# Peripherals.net
KiCad netlist of a schematic drawn in Altium Designer
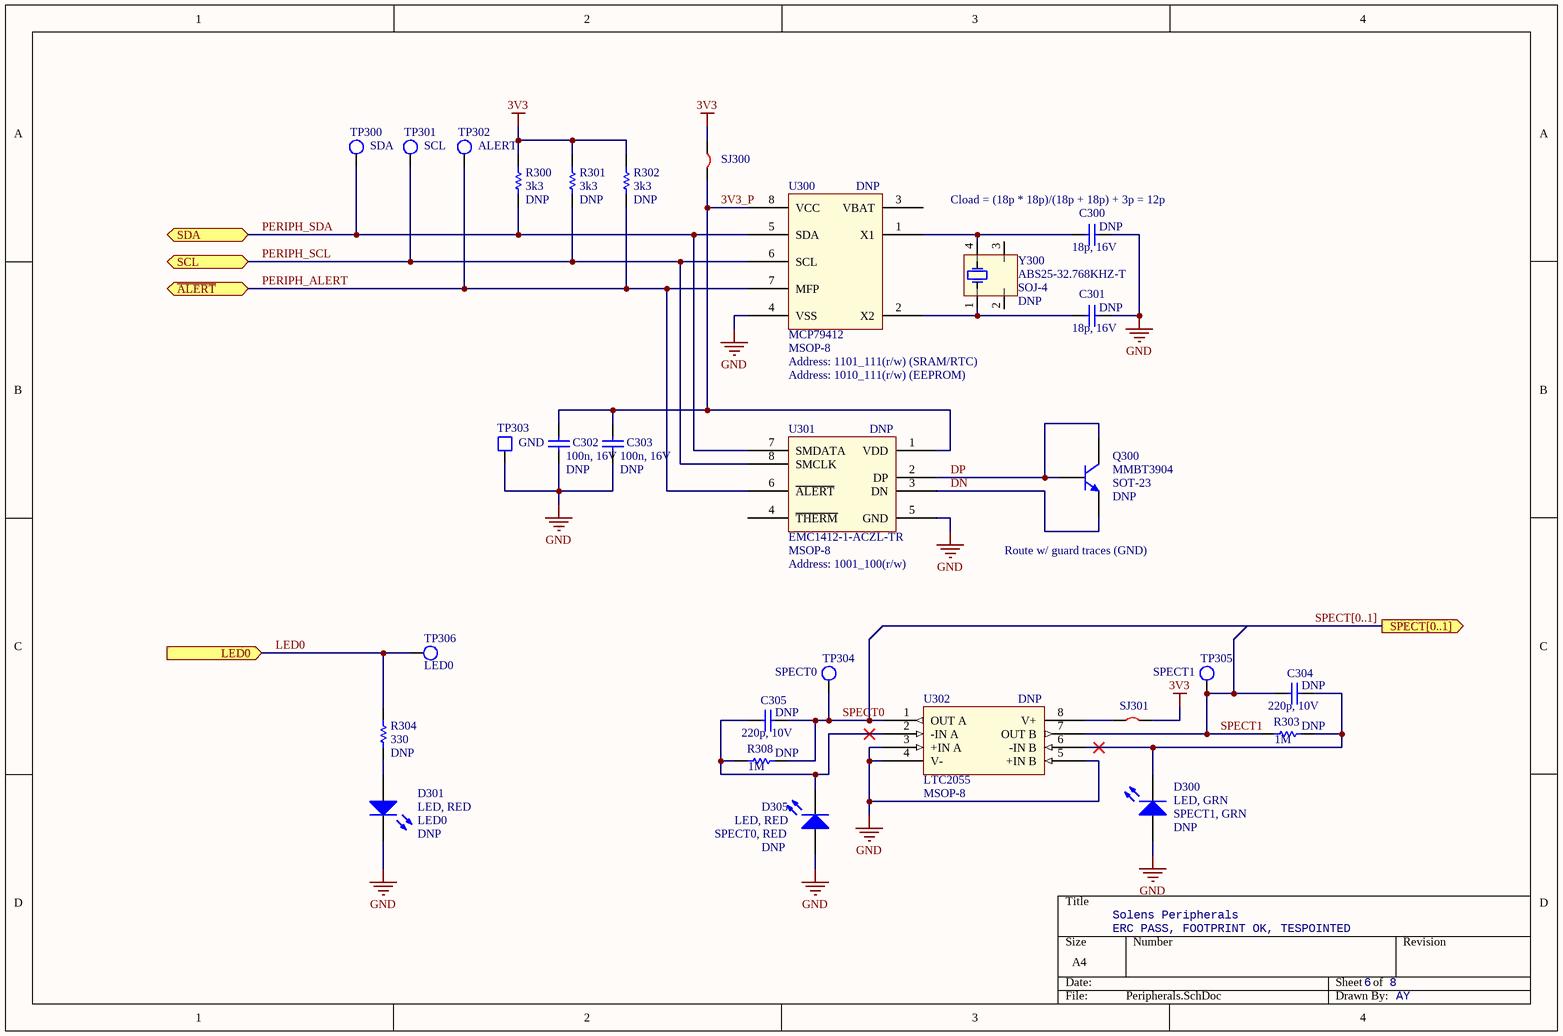
[diagram p0: Peripherals.SchDoc]

(export (version "E")
  (design (tool "Eeschema 10.0.6"))
  (components
    (comp (ref "C300")
      (value "18p, 16V")
      (footprint "CAP_0402")
      (description "Capacitor")
      (fields (field (name "DNP") "DNP") (field (name "Comment") "18p, 16V, 0402 (DNP)"))
      (libsource (lib "Miscellaneous Devices") (part "Cap"))
    )
    (comp (ref "C301")
      (value "18p, 16V")
      (footprint "CAP_0402")
      (description "Capacitor")
      (fields (field (name "DNP") "DNP") (field (name "Comment") "18p, 16V, 0402 (DNP)"))
      (libsource (lib "Miscellaneous Devices") (part "Cap"))
    )
    (comp (ref "C302")
      (value "100n, 16V")
      (footprint "CAP_0402")
      (description "Capacitor")
      (fields (field (name "DNP") "DNP") (field (name "Comment") "100n, 16V, 0402 (DNP)"))
      (libsource (lib "Miscellaneous Devices") (part "Cap"))
    )
    (comp (ref "C303")
      (value "100n, 16V")
      (footprint "CAP_0402")
      (description "Capacitor")
      (fields (field (name "DNP") "DNP") (field (name "Comment") "100n, 16V, 0402 (DNP)"))
      (libsource (lib "Miscellaneous Devices") (part "Cap"))
    )
    (comp (ref "C304")
      (value "220p, 10V")
      (footprint "CAP_0402")
      (description "Capacitor")
      (fields (field (name "DNP") "DNP") (field (name "Comment") "220p, 16V, 0402 (DNP)"))
      (libsource (lib "Miscellaneous Devices") (part "Cap"))
    )
    (comp (ref "C305")
      (value "220p, 10V")
      (footprint "CAP_0402")
      (description "Capacitor")
      (fields (field (name "DNP") "DNP") (field (name "Comment") "220p, 16V, 0402 (DNP)"))
      (libsource (lib "Miscellaneous Devices") (part "Cap"))
    )
    (comp (ref "D300")
      (value "LED, GRN")
      (footprint "LED_0603")
      (description "Typical INFRARED GaAs LED")
      (fields
        (field (name "DNP") "DNP")
        (field (name "FUNCTION") "SPECT1, GRN")
        (field (name "Comment") "LED, GRN, 0603 (DNP)")
      )
      (libsource (lib "Miscellaneous Devices") (part "LED0"))
    )
    (comp (ref "D301")
      (value "LED, RED")
      (footprint "LED_0603")
      (description "Typical INFRARED GaAs LED")
      (fields
        (field (name "DNP") "DNP")
        (field (name "FUNCTION") "LED0")
        (field (name "Comment") "LED, RED, 0603 (DNP)")
      )
      (libsource (lib "Miscellaneous Devices") (part "LED0"))
    )
    (comp (ref "D305")
      (value "LED, RED")
      (footprint "LED_0603")
      (description "Typical INFRARED GaAs LED")
      (fields
        (field (name "DNP") "DNP")
        (field (name "FUNCTION") "SPECT0, RED")
        (field (name "Comment") "LED, RED, 0603 (DNP)")
      )
      (libsource (lib "Miscellaneous Devices") (part "LED0"))
    )
    (comp (ref "Q300")
      (value "MMBT3904, SOT-23 (DNP)")
      (footprint "SOT90P240X110-3N")
      (description "NPN General Purpose Amplifier")
      (fields
        (field (name "PARTNUMBER") "MMBT3904")
        (field (name "PACKAGENAME") "SOT-23")
        (field (name "DNP") "DNP")
      )
      (libsource (lib "Miscellaneous Devices") (part "2N3904"))
    )
    (comp (ref "R300")
      (value "3k3")
      (footprint "RES_0805")
      (description "Resistor")
      (fields (field (name "DNP") "DNP") (field (name "Comment") "3k3, 1/8W, 0805 (DNP)"))
      (libsource (lib "Miscellaneous Devices") (part "Res1"))
    )
    (comp (ref "R301")
      (value "3k3")
      (footprint "RES_0805")
      (description "Resistor")
      (fields (field (name "DNP") "DNP") (field (name "Comment") "3k3, 1/8W, 0805 (DNP)"))
      (libsource (lib "Miscellaneous Devices") (part "Res1"))
    )
    (comp (ref "R302")
      (value "3k3")
      (footprint "RES_0805")
      (description "Resistor")
      (fields (field (name "DNP") "DNP") (field (name "Comment") "3k3, 1/8W, 0805 (DNP)"))
      (libsource (lib "Miscellaneous Devices") (part "Res1"))
    )
    (comp (ref "R303")
      (value "1M")
      (footprint "RES_0402")
      (description "Resistor")
      (fields (field (name "DNP") "DNP") (field (name "Comment") "1M, 1/16W, 0402 (DNP)"))
      (libsource (lib "Miscellaneous Devices") (part "Res1"))
    )
    (comp (ref "R304")
      (value "330")
      (footprint "RES_0805")
      (description "Resistor")
      (fields (field (name "DNP") "DNP") (field (name "Comment") "330, 1/8W, 0805 (DNP)"))
      (libsource (lib "Miscellaneous Devices") (part "Res1"))
    )
    (comp (ref "R308")
      (value "1M")
      (footprint "RES_0402")
      (description "Resistor")
      (fields (field (name "DNP") "DNP") (field (name "Comment") "1M, 1/16W, 0402 (DNP)"))
      (libsource (lib "Miscellaneous Devices") (part "Res1"))
    )
    (comp (ref "SJ300")
      (value "SJ, 0805 (DNP)")
      (footprint "SJ_0805")
      (description "Solder jumper")
      (libsource (lib "Schlib1") (part "SJ"))
    )
    (comp (ref "SJ301")
      (value "SJ, 0805 (DNP)")
      (footprint "SJ_0805")
      (description "Solder jumper")
      (libsource (lib "Schlib1") (part "SJ"))
    )
    (comp (ref "TP300")
      (value "TP (DNP)")
      (footprint "TP_SMALL")
      (fields (field (name "VISIBLENETNAME") "SDA"))
      (libsource (lib "Schlib1") (part "TP_SMALL"))
    )
    (comp (ref "TP301")
      (value "TP (DNP)")
      (footprint "TP_SMALL")
      (fields (field (name "VISIBLENETNAME") "SCL"))
      (libsource (lib "Schlib1") (part "TP_SMALL"))
    )
    (comp (ref "TP302")
      (value "TP (DNP)")
      (footprint "TP_SMALL")
      (fields (field (name "VISIBLENETNAME") "ALERT"))
      (libsource (lib "Schlib1") (part "TP_SMALL"))
    )
    (comp (ref "TP303")
      (value "TP (DNP)")
      (footprint "TP_LARGE")
      (fields (field (name "VISIBLENETNAME") "GND"))
      (libsource (lib "Schlib1") (part "TP_LARGE"))
    )
    (comp (ref "TP304")
      (value "TP (DNP)")
      (footprint "TP_SMALL")
      (fields (field (name "VISIBLENETNAME") "SPECT0"))
      (libsource (lib "Schlib1") (part "TP_SMALL"))
    )
    (comp (ref "TP305")
      (value "TP (DNP)")
      (footprint "TP_SMALL")
      (fields (field (name "VISIBLENETNAME") "SPECT1"))
      (libsource (lib "Schlib1") (part "TP_SMALL"))
    )
    (comp (ref "TP306")
      (value "TP (DNP)")
      (footprint "TP_SMALL")
      (fields (field (name "VISIBLENETNAME") "LED0"))
      (libsource (lib "Schlib1") (part "TP_SMALL"))
    )
    (comp (ref "U300")
      (value "MCP79412, MSOP-8 (DNP)")
      (footprint "TSOP65P490X110-8N")
      (description "I2C RTC w/ SRAM and EEPROM")
      (fields
        (field (name "PACKAGENAME") "MSOP-8")
        (field (name "PARTNUMBER") "MCP79412")
        (field (name "DNP") "DNP")
      )
      (libsource (lib "Schlib1") (part "MCP7941x"))
    )
    (comp (ref "U301")
      (value "EMC1412, MSOP-8 (DNP)")
      (footprint "TSOP65P490X110-8N")
      (description "Dual channel I2C temperature sensor")
      (fields
        (field (name "PARTNUMBER") "EMC1412-1-ACZL-TR")
        (field (name "PACKAGENAME") "MSOP-8")
        (field (name "DNP") "DNP")
      )
      (libsource (lib "Schlib1") (part "EMC1412"))
    )
    (comp (ref "U302")
      (value "LTC2055, MSOP-8 (DNP)")
      (footprint "TSOP65P490X110-8N")
      (description "Dual zero-drift op amp")
      (fields
        (field (name "PARTNUMBER") "LTC2055")
        (field (name "PACKAGENAME") "MSOP-8")
        (field (name "DNP") "DNP")
      )
      (libsource (lib "Schlib1") (part "LTC2054/LTC2055"))
    )
    (comp (ref "Y300")
      (value "ABS25-32.768KHZ-T (DNP)")
      (footprint "XTAL-SOJ-4")
      (fields
        (field (name "PARTNUMBER") "ABS25-32.768KHZ-T")
        (field (name "PACKAGENAME") "SOJ-4")
        (field (name "DNP") "DNP")
      )
      (libsource (lib "Schlib1") (part "XTAL-SOJ-4"))
    )
  )
  (nets
    (net (code "1") (name "/3V3_P") (class "Default")
      (node (ref "C302") (pin "1") (pinfunction "1_1") (pintype "passive"))
      (node (ref "C303") (pin "1") (pinfunction "1_1") (pintype "passive"))
      (node (ref "SJ300") (pin "2") (pinfunction "2_2") (pintype "passive"))
      (node (ref "U300") (pin "8") (pinfunction "VCC_8") (pintype "power_in"))
      (node (ref "U301") (pin "1") (pinfunction "VDD_1") (pintype "power_in"))
    )
    (net (code "2") (name "/DN") (class "Default")
      (node (ref "Q300") (pin "1") (pinfunction "E_1") (pintype "passive"))
      (node (ref "U301") (pin "3") (pinfunction "DN_3") (pintype "passive"))
    )
    (net (code "3") (name "/DP") (class "Default")
      (node (ref "Q300") (pin "2") (pinfunction "B_2") (pintype "passive"))
      (node (ref "Q300") (pin "3") (pinfunction "C_3") (pintype "passive"))
      (node (ref "U301") (pin "2") (pinfunction "DP_2") (pintype "passive"))
    )
    (net (code "4") (name "/LED0") (class "Default")
      (node (ref "R304") (pin "1") (pinfunction "1_1") (pintype "passive"))
      (node (ref "TP306") (pin "1") (pinfunction "1_1") (pintype "passive"))
    )
    (net (code "5") (name "/PERIPH_ALERT") (class "Default")
      (node (ref "R302") (pin "2") (pinfunction "2_2") (pintype "passive"))
      (node (ref "TP302") (pin "1") (pinfunction "1_1") (pintype "passive"))
      (node (ref "U300") (pin "7") (pinfunction "MFP_7") (pintype "open_collector"))
      (node (ref "U301") (pin "6") (pinfunction "~{ALERT}_6") (pintype "open_collector"))
    )
    (net (code "6") (name "/PERIPH_SCL") (class "Default")
      (node (ref "R301") (pin "2") (pinfunction "2_2") (pintype "passive"))
      (node (ref "TP301") (pin "1") (pinfunction "1_1") (pintype "passive"))
      (node (ref "U300") (pin "6") (pinfunction "SCL_6") (pintype "open_collector"))
      (node (ref "U301") (pin "8") (pinfunction "SMCLK_8") (pintype "open_collector"))
    )
    (net (code "7") (name "/PERIPH_SDA") (class "Default")
      (node (ref "R300") (pin "2") (pinfunction "2_2") (pintype "passive"))
      (node (ref "TP300") (pin "1") (pinfunction "1_1") (pintype "passive"))
      (node (ref "U300") (pin "5") (pinfunction "SDA_5") (pintype "open_collector"))
      (node (ref "U301") (pin "7") (pinfunction "SMDATA_7") (pintype "open_collector"))
    )
    (net (code "8") (name "/SPECT0") (class "Default")
      (node (ref "C305") (pin "2") (pinfunction "2_2") (pintype "passive"))
      (node (ref "R308") (pin "2") (pinfunction "2_2") (pintype "passive"))
      (node (ref "TP304") (pin "1") (pinfunction "1_1") (pintype "passive"))
      (node (ref "U302") (pin "1") (pinfunction "OUT_A_1") (pintype "output"))
    )
    (net (code "9") (name "/SPECT1") (class "Default")
      (node (ref "C304") (pin "1") (pinfunction "1_1") (pintype "passive"))
      (node (ref "R303") (pin "1") (pinfunction "1_1") (pintype "passive"))
      (node (ref "TP305") (pin "1") (pinfunction "1_1") (pintype "passive"))
      (node (ref "U302") (pin "7") (pinfunction "OUT_B_7") (pintype "output"))
    )
    (net (code "11") (name "3V3") (class "Default")
      (node (ref "R300") (pin "1") (pinfunction "1_1") (pintype "passive"))
      (node (ref "R301") (pin "1") (pinfunction "1_1") (pintype "passive"))
      (node (ref "R302") (pin "1") (pinfunction "1_1") (pintype "passive"))
      (node (ref "SJ300") (pin "1") (pinfunction "1_1") (pintype "passive"))
      (node (ref "SJ301") (pin "2") (pinfunction "2_2") (pintype "passive"))
    )
    (net (code "12") (name "GND") (class "Default")
      (node (ref "C300") (pin "2") (pinfunction "2_2") (pintype "passive"))
      (node (ref "C301") (pin "2") (pinfunction "2_2") (pintype "passive"))
      (node (ref "C302") (pin "2") (pinfunction "2_2") (pintype "passive"))
      (node (ref "C303") (pin "2") (pinfunction "2_2") (pintype "passive"))
      (node (ref "D300") (pin "1") (pinfunction "A_1") (pintype "passive"))
      (node (ref "D301") (pin "2") (pinfunction "K_2") (pintype "passive"))
      (node (ref "D305") (pin "1") (pinfunction "A_1") (pintype "passive"))
      (node (ref "TP303") (pin "1") (pinfunction "1_1") (pintype "passive"))
      (node (ref "U300") (pin "4") (pinfunction "VSS_4") (pintype "power_in"))
      (node (ref "U301") (pin "5") (pinfunction "GND_5") (pintype "power_in"))
      (node (ref "U302") (pin "3") (pinfunction "+IN_A_3") (pintype "input"))
      (node (ref "U302") (pin "4") (pinfunction "V-_4") (pintype "power_in"))
      (node (ref "U302") (pin "5") (pinfunction "+IN_B_5") (pintype "input"))
    )
    (net (code "13") (name "Net-(D300-K)") (class "Default")
      (node (ref "C304") (pin "2") (pinfunction "2_2") (pintype "passive"))
      (node (ref "D300") (pin "2") (pinfunction "K_2") (pintype "passive"))
      (node (ref "R303") (pin "2") (pinfunction "2_2") (pintype "passive"))
      (node (ref "U302") (pin "6") (pinfunction "-IN_B_6") (pintype "input"))
    )
    (net (code "14") (name "Net-(D301-A)") (class "Default")
      (node (ref "D301") (pin "1") (pinfunction "A_1") (pintype "passive"))
      (node (ref "R304") (pin "2") (pinfunction "2_2") (pintype "passive"))
    )
    (net (code "15") (name "Net-(D305-K)") (class "Default")
      (node (ref "C305") (pin "1") (pinfunction "1_1") (pintype "passive"))
      (node (ref "D305") (pin "2") (pinfunction "K_2") (pintype "passive"))
      (node (ref "R308") (pin "1") (pinfunction "1_1") (pintype "passive"))
      (node (ref "U302") (pin "2") (pinfunction "-IN_A_2") (pintype "input"))
    )
    (net (code "16") (name "Net-(U300-X1)") (class "Default")
      (node (ref "C300") (pin "1") (pinfunction "1_1") (pintype "passive"))
      (node (ref "U300") (pin "1") (pinfunction "X1_1") (pintype "passive"))
      (node (ref "Y300") (pin "4") (pinfunction "4_4") (pintype "passive"))
    )
    (net (code "17") (name "Net-(U300-X2)") (class "Default")
      (node (ref "C301") (pin "1") (pinfunction "1_1") (pintype "passive"))
      (node (ref "U300") (pin "2") (pinfunction "X2_2") (pintype "passive"))
      (node (ref "Y300") (pin "1") (pinfunction "1_1") (pintype "passive"))
    )
    (net (code "18") (name "Net-(U302-V+)") (class "Default")
      (node (ref "SJ301") (pin "1") (pinfunction "1_1") (pintype "passive"))
      (node (ref "U302") (pin "8") (pinfunction "V+_8") (pintype "power_in"))
    )
    (net (code "19") (name "unconnected-(U300-VBAT-Pad3)") (class "Default")
      (node (ref "U300") (pin "3") (pinfunction "VBAT_3") (pintype "power_in"))
    )
    (net (code "20") (name "unconnected-(U301-~{THERM}-Pad4)") (class "Default")
      (node (ref "U301") (pin "4") (pinfunction "~{THERM}_4") (pintype "open_collector"))
    )
    (net (code "21") (name "unconnected-(Y300-Pad2)") (class "Default")
      (node (ref "Y300") (pin "2") (pinfunction "2_2") (pintype "passive"))
    )
    (net (code "22") (name "unconnected-(Y300-Pad3)") (class "Default")
      (node (ref "Y300") (pin "3") (pinfunction "3_3") (pintype "passive"))
    )
  )
)
